# photo_sensor.net
KiCad netlist of a schematic drawn in EAGLE
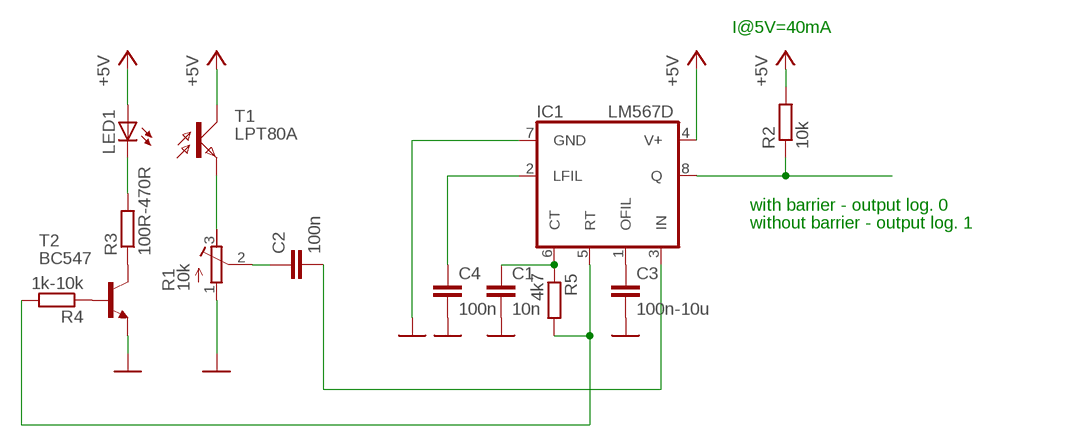
[diagram p0: schematic, sheet 1]

(export (version "E")
  (design (tool "Eeschema 10.0.6"))
  (components
    (comp (ref "C1")
      (value "10n")
      (footprint "eagle-import:0805")
      (libsource (lib "eagle-import") (part "C0805"))
    )
    (comp (ref "C2")
      (value "100n")
      (footprint "eagle-import:0805")
      (libsource (lib "eagle-import") (part "C0805"))
    )
    (comp (ref "C3")
      (value "100n-10u")
      (footprint "eagle-import:0805")
      (libsource (lib "eagle-import") (part "C0805"))
    )
    (comp (ref "C4")
      (value "100n")
      (footprint "eagle-import:0805")
      (libsource (lib "eagle-import") (part "C0805"))
    )
    (comp (ref "IC1")
      (value "LM567D")
      (footprint "eagle-import:SO08")
      (libsource (lib "eagle-import") (part "567DLM"))
    )
    (comp (ref "LED1")
      (value "LED3MM")
      (footprint "eagle-import:LED3MM")
      (libsource (lib "eagle-import") (part "LED3MM"))
    )
    (comp (ref "R1")
      (value "10k")
      (footprint "eagle-import:RTRIM3202")
      (libsource (lib "eagle-import") (part "R-TRIMM3202"))
    )
    (comp (ref "R2")
      (value "10k")
      (footprint "eagle-import:0805")
      (libsource (lib "eagle-import") (part "R0805"))
    )
    (comp (ref "R3")
      (value "100R-470R")
      (footprint "eagle-import:0805")
      (libsource (lib "eagle-import") (part "R0805"))
    )
    (comp (ref "R4")
      (value "1k-10k")
      (footprint "eagle-import:0805")
      (libsource (lib "eagle-import") (part "R0805"))
    )
    (comp (ref "R5")
      (value "4k7")
      (footprint "eagle-import:0805")
      (libsource (lib "eagle-import") (part "R0805"))
    )
    (comp (ref "T1")
      (value "LPT80A")
      (footprint "eagle-import:LPT80A")
      (libsource (lib "eagle-import") (part "LPT80A"))
    )
    (comp (ref "T2")
      (value "BC547")
      (footprint "eagle-import:TO92")
      (libsource (lib "eagle-import") (part "BC547"))
    )
  )
  (nets
    (net (code "1") (name "+5V") (class "Default")
      (node (ref "IC1") (pin "4") (pinfunction "V+_4") (pintype "power_in"))
      (node (ref "LED1") (pin "A") (pinfunction "A_A") (pintype "passive"))
      (node (ref "R2") (pin "2") (pinfunction "2_2") (pintype "passive"))
      (node (ref "T1") (pin "C") (pinfunction "C_C") (pintype "passive"))
    )
    (net (code "2") (name "GND") (class "Default")
      (node (ref "C1") (pin "2") (pinfunction "2_2") (pintype "passive"))
      (node (ref "C3") (pin "2") (pinfunction "2_2") (pintype "passive"))
      (node (ref "C4") (pin "2") (pinfunction "2_2") (pintype "passive"))
      (node (ref "IC1") (pin "7") (pinfunction "GND_7") (pintype "power_in"))
      (node (ref "R1") (pin "1") (pinfunction "A_1") (pintype "passive"))
      (node (ref "T2") (pin "1") (pinfunction "E_1") (pintype "passive"))
    )
    (net (code "3") (name "Net-(IC1-CT)") (class "Default")
      (node (ref "C1") (pin "1") (pinfunction "1_1") (pintype "passive"))
      (node (ref "IC1") (pin "6") (pinfunction "CT_6") (pintype "passive"))
      (node (ref "R5") (pin "1") (pinfunction "1_1") (pintype "passive"))
    )
    (net (code "4") (name "Net-(IC1-IN)") (class "Default")
      (node (ref "C2") (pin "2") (pinfunction "2_2") (pintype "passive"))
      (node (ref "IC1") (pin "3") (pinfunction "IN_3") (pintype "input"))
    )
    (net (code "5") (name "Net-(IC1-LFIL)") (class "Default")
      (node (ref "C4") (pin "1") (pinfunction "1_1") (pintype "passive"))
      (node (ref "IC1") (pin "2") (pinfunction "LFIL_2") (pintype "passive"))
    )
    (net (code "6") (name "Net-(IC1-OFIL)") (class "Default")
      (node (ref "C3") (pin "1") (pinfunction "1_1") (pintype "passive"))
      (node (ref "IC1") (pin "1") (pinfunction "OFIL_1") (pintype "output"))
    )
    (net (code "7") (name "Net-(IC1-Q)") (class "Default")
      (node (ref "IC1") (pin "8") (pinfunction "Q_8") (pintype "output"))
      (node (ref "R2") (pin "1") (pinfunction "1_1") (pintype "passive"))
    )
    (net (code "8") (name "Net-(IC1-RT)") (class "Default")
      (node (ref "IC1") (pin "5") (pinfunction "RT_5") (pintype "passive"))
      (node (ref "R4") (pin "2") (pinfunction "2_2") (pintype "passive"))
      (node (ref "R5") (pin "2") (pinfunction "2_2") (pintype "passive"))
    )
    (net (code "9") (name "Net-(LED1-C)") (class "Default")
      (node (ref "LED1") (pin "K") (pinfunction "C_K") (pintype "passive"))
      (node (ref "R3") (pin "2") (pinfunction "2_2") (pintype "passive"))
    )
    (net (code "10") (name "Net-(R1-E)") (class "Default")
      (node (ref "R1") (pin "3") (pinfunction "E_3") (pintype "passive"))
      (node (ref "T1") (pin "E") (pinfunction "E_E") (pintype "passive"))
    )
    (net (code "11") (name "Net-(R1-S)") (class "Default")
      (node (ref "C2") (pin "1") (pinfunction "1_1") (pintype "passive"))
      (node (ref "R1") (pin "2") (pinfunction "S_2") (pintype "passive"))
    )
    (net (code "12") (name "Net-(T2-B)") (class "Default")
      (node (ref "R4") (pin "1") (pinfunction "1_1") (pintype "passive"))
      (node (ref "T2") (pin "2") (pinfunction "B_2") (pintype "passive"))
    )
    (net (code "13") (name "Net-(T2-C)") (class "Default")
      (node (ref "R3") (pin "1") (pinfunction "1_1") (pintype "passive"))
      (node (ref "T2") (pin "3") (pinfunction "C_3") (pintype "passive"))
    )
  )
)
